# v3_Tensegrity_Motherboard.net
KiCad netlist of a schematic drawn in EAGLE
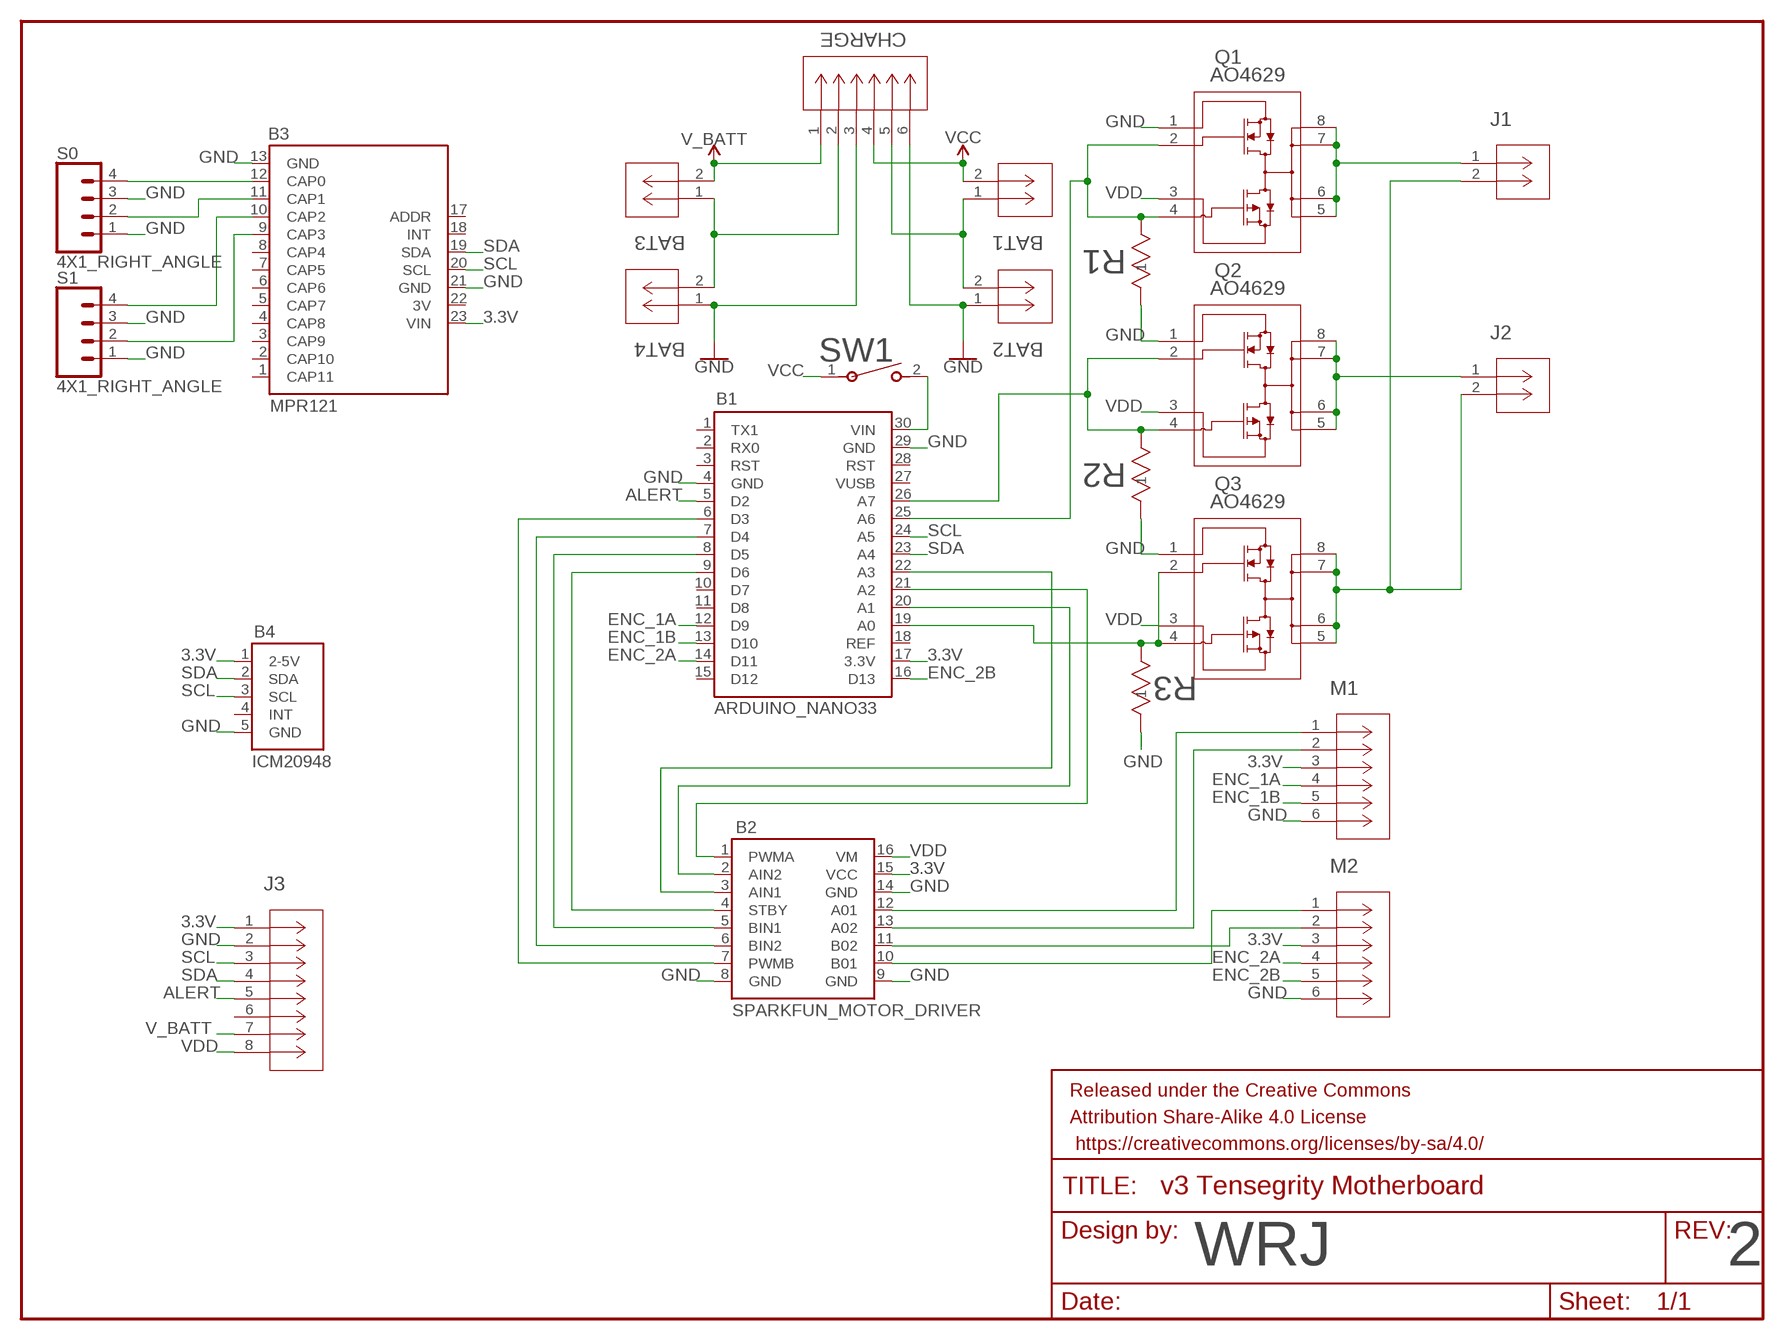
[diagram p0: schematic, sheet 1]

(export (version "E")
  (design (tool "Eeschema 10.0.6"))
  (components
    (comp (ref "B1")
      (value "ARDUINO_NANO33")
      (footprint "eagle-import:HDRVR30W64P1524X254_2X15_3810X1778X851B")
      (libsource (lib "eagle-import") (part "ARDUINO_NANO33"))
    )
    (comp (ref "B2")
      (value "SPARKFUN_MOTOR_DRIVER")
      (footprint "eagle-import:HDRVR16W64P1524X254_2X8_2032X2032X254B")
      (libsource (lib "eagle-import") (part "SPARKFUN_MOTOR_DRIVER"))
    )
    (comp (ref "B3")
      (value "MPR121")
      (footprint "eagle-import:HDRVR26W64P1524X254_2X13_3302X1905X851B")
      (libsource (lib "eagle-import") (part "MPR121"))
    )
    (comp (ref "B4")
      (value "ICM20948")
      (footprint "eagle-import:HDRVR5W64P254_1X5_1270X254X851B")
      (libsource (lib "eagle-import") (part "ICM20948"))
    )
    (comp (ref "BAT1")
      (value "S2B-PH-K-S(LF)(SN)")
      (footprint "eagle-import:CONN_S2B-PH-K-S_JST")
      (fields (field (name "COPYRIGHT") "Copyright (C) 2024 Ultra Librarian. All rights reserved."))
      (libsource (lib "eagle-import") (part "S2B-PH-K-S(LF)(SN)"))
    )
    (comp (ref "BAT2")
      (value "S2B-PH-K-S(LF)(SN)")
      (footprint "eagle-import:CONN_S2B-PH-K-S_JST")
      (fields (field (name "COPYRIGHT") "Copyright (C) 2024 Ultra Librarian. All rights reserved."))
      (libsource (lib "eagle-import") (part "S2B-PH-K-S(LF)(SN)"))
    )
    (comp (ref "BAT3")
      (value "S2B-PH-K-S(LF)(SN)")
      (footprint "eagle-import:CONN_S2B-PH-K-S_JST")
      (fields (field (name "COPYRIGHT") "Copyright (C) 2024 Ultra Librarian. All rights reserved."))
      (libsource (lib "eagle-import") (part "S2B-PH-K-S(LF)(SN)"))
    )
    (comp (ref "BAT4")
      (value "S2B-PH-K-S(LF)(SN)")
      (footprint "eagle-import:CONN_S2B-PH-K-S_JST")
      (fields (field (name "COPYRIGHT") "Copyright (C) 2024 Ultra Librarian. All rights reserved."))
      (libsource (lib "eagle-import") (part "S2B-PH-K-S(LF)(SN)"))
    )
    (comp (ref "CHARGE")
      (value "S6B-XH-A")
      (footprint "eagle-import:CONN_S6B-XH-A_JST")
      (fields (field (name "COPYRIGHT") "Copyright (C) 2024 Ultra Librarian. All rights reserved."))
      (libsource (lib "eagle-import") (part "S6B-XH-A"))
    )
    (comp (ref "FRAME1")
      (value "FRAME-LETTER")
      (footprint "eagle-import:CREATIVE_COMMONS")
      (libsource (lib "eagle-import") (part "FRAME-LETTER"))
    )
    (comp (ref "J1")
      (value "S2B-XH-A-1(LF)(SN)")
      (footprint "eagle-import:CONN_S2B-XH-A-1(LF)(SN)_JST")
      (fields (field (name "COPYRIGHT") "Copyright (C) 2024 Ultra Librarian. All rights reserved."))
      (libsource (lib "eagle-import") (part "S2B-XH-A-1(LF)(SN)"))
    )
    (comp (ref "J2")
      (value "S2B-XH-A-1(LF)(SN)")
      (footprint "eagle-import:CONN_S2B-XH-A-1(LF)(SN)_JST")
      (fields (field (name "COPYRIGHT") "Copyright (C) 2024 Ultra Librarian. All rights reserved."))
      (libsource (lib "eagle-import") (part "S2B-XH-A-1(LF)(SN)"))
    )
    (comp (ref "J3")
      (value "PEC08SAAN")
      (footprint "eagle-import:CONN_XXC08SAAN_SUL")
      (fields (field (name "COPYRIGHT") "Copyright (C) 2024 Ultra Librarian. All rights reserved."))
      (libsource (lib "eagle-import") (part "PEC08SAAN"))
    )
    (comp (ref "M1")
      (value "BM06B-SRSS-TB(LF)(SN)")
      (footprint "eagle-import:CONN_BM06B-SRSS-TB_JST")
      (fields (field (name "COPYRIGHT") "Copyright (C) 2024 Ultra Librarian. All rights reserved."))
      (libsource (lib "eagle-import") (part "BM06B-SRSS-TB(LF)(SN)"))
    )
    (comp (ref "M2")
      (value "BM06B-SRSS-TB(LF)(SN)")
      (footprint "eagle-import:CONN_BM06B-SRSS-TB_JST")
      (fields (field (name "COPYRIGHT") "Copyright (C) 2024 Ultra Librarian. All rights reserved."))
      (libsource (lib "eagle-import") (part "BM06B-SRSS-TB(LF)(SN)"))
    )
    (comp (ref "Q1")
      (value "AO4629")
      (footprint "eagle-import:SO8(SOP-8L)_AOS")
      (fields (field (name "COPYRIGHT") "Copyright (C) 2024 Ultra Librarian. All rights reserved."))
      (libsource (lib "eagle-import") (part "AO4629"))
    )
    (comp (ref "Q2")
      (value "AO4629")
      (footprint "eagle-import:SO8(SOP-8L)_AOS")
      (fields (field (name "COPYRIGHT") "Copyright (C) 2024 Ultra Librarian. All rights reserved."))
      (libsource (lib "eagle-import") (part "AO4629"))
    )
    (comp (ref "Q3")
      (value "AO4629")
      (footprint "eagle-import:SO8(SOP-8L)_AOS")
      (fields (field (name "COPYRIGHT") "Copyright (C) 2024 Ultra Librarian. All rights reserved."))
      (libsource (lib "eagle-import") (part "AO4629"))
    )
    (comp (ref "R1")
      (value "RC0603FR-071KL")
      (footprint "eagle-import:RC0603N_YAG")
      (fields (field (name "COPYRIGHT") "Copyright (C) 2024 Ultra Librarian. All rights reserved."))
      (libsource (lib "eagle-import") (part "RC0603FR-071KL"))
    )
    (comp (ref "R2")
      (value "RC0603FR-071KL")
      (footprint "eagle-import:RC0603N_YAG")
      (fields (field (name "COPYRIGHT") "Copyright (C) 2024 Ultra Librarian. All rights reserved."))
      (libsource (lib "eagle-import") (part "RC0603FR-071KL"))
    )
    (comp (ref "R3")
      (value "RC0603FR-071KL")
      (footprint "eagle-import:RC0603N_YAG")
      (fields (field (name "COPYRIGHT") "Copyright (C) 2024 Ultra Librarian. All rights reserved."))
      (libsource (lib "eagle-import") (part "RC0603FR-071KL"))
    )
    (comp (ref "S0")
      (value "4X1_RIGHT_ANGLE")
      (footprint "eagle-import:HDRRA4W64P254_1X4_1016X254X278B")
      (libsource (lib "eagle-import") (part "4X1_RIGHT_ANGLE"))
    )
    (comp (ref "S1")
      (value "4X1_RIGHT_ANGLE")
      (footprint "eagle-import:HDRRA4W64P254_1X4_1016X254X278B")
      (libsource (lib "eagle-import") (part "4X1_RIGHT_ANGLE"))
    )
    (comp (ref "SW1")
      (value "GPTS203212B")
      (footprint "eagle-import:SW_GPTS203212B_CWI")
      (fields (field (name "COPYRIGHT") "Copyright (C) 2024 Ultra Librarian. All rights reserved."))
      (libsource (lib "eagle-import") (part "GPTS203212B"))
    )
  )
  (nets
    (net (code "1") (name "/3.3V") (class "Default")
      (node (ref "B1") (pin "17") (pinfunction "3.3V_17") (pintype "power_in"))
      (node (ref "B2") (pin "15") (pinfunction "VCC_15") (pintype "power_in"))
      (node (ref "B3") (pin "23") (pinfunction "VIN_23") (pintype "power_in"))
      (node (ref "B4") (pin "1") (pinfunction "2-5V_1") (pintype "power_in"))
      (node (ref "J3") (pin "1") (pinfunction "1_1") (pintype "passive"))
      (node (ref "M1") (pin "3") (pinfunction "3_3") (pintype "passive"))
      (node (ref "M2") (pin "3") (pinfunction "3_3") (pintype "passive"))
    )
    (net (code "2") (name "/3V") (class "Default")
      (node (ref "B3") (pin "22") (pinfunction "3V_22") (pintype "power_in"))
    )
    (net (code "3") (name "/ALERT") (class "Default")
      (node (ref "B1") (pin "5") (pinfunction "D2_5") (pintype "bidirectional"))
      (node (ref "J3") (pin "5") (pinfunction "5_5") (pintype "passive"))
    )
    (net (code "4") (name "/ENC_1A") (class "Default")
      (node (ref "B1") (pin "12") (pinfunction "D9_12") (pintype "bidirectional"))
      (node (ref "M1") (pin "4") (pinfunction "4_4") (pintype "passive"))
    )
    (net (code "5") (name "/ENC_1B") (class "Default")
      (node (ref "B1") (pin "13") (pinfunction "D10_13") (pintype "bidirectional"))
      (node (ref "M1") (pin "5") (pinfunction "5_5") (pintype "passive"))
    )
    (net (code "6") (name "/ENC_2A") (class "Default")
      (node (ref "B1") (pin "14") (pinfunction "D11_14") (pintype "bidirectional"))
      (node (ref "M2") (pin "4") (pinfunction "4_4") (pintype "passive"))
    )
    (net (code "7") (name "/ENC_2B") (class "Default")
      (node (ref "B1") (pin "16") (pinfunction "D13_16") (pintype "bidirectional"))
      (node (ref "M2") (pin "5") (pinfunction "5_5") (pintype "passive"))
    )
    (net (code "8") (name "/SCL") (class "Default")
      (node (ref "B1") (pin "24") (pinfunction "A5_24") (pintype "bidirectional"))
      (node (ref "B3") (pin "20") (pinfunction "SCL_20") (pintype "bidirectional"))
      (node (ref "B4") (pin "3") (pinfunction "SCL_3") (pintype "bidirectional"))
      (node (ref "J3") (pin "3") (pinfunction "3_3") (pintype "passive"))
    )
    (net (code "9") (name "/SDA") (class "Default")
      (node (ref "B1") (pin "23") (pinfunction "A4_23") (pintype "bidirectional"))
      (node (ref "B3") (pin "19") (pinfunction "SDA_19") (pintype "bidirectional"))
      (node (ref "B4") (pin "2") (pinfunction "SDA_2") (pintype "bidirectional"))
      (node (ref "J3") (pin "4") (pinfunction "4_4") (pintype "passive"))
    )
    (net (code "10") (name "/VDD") (class "Default")
      (node (ref "B2") (pin "16") (pinfunction "VM_16") (pintype "power_in"))
      (node (ref "J3") (pin "8") (pinfunction "8_8") (pintype "passive"))
      (node (ref "Q1") (pin "3") (pinfunction "3_3") (pintype "passive"))
      (node (ref "Q2") (pin "3") (pinfunction "3_3") (pintype "passive"))
      (node (ref "Q3") (pin "3") (pinfunction "3_3") (pintype "passive"))
    )
    (net (code "11") (name "/VUSB") (class "Default")
      (node (ref "B1") (pin "27") (pinfunction "VUSB_27") (pintype "power_in"))
    )
    (net (code "12") (name "GND") (class "Default")
      (node (ref "B1") (pin "29") (pinfunction "GND_29") (pintype "power_in"))
      (node (ref "B1") (pin "4") (pinfunction "GND_4") (pintype "power_in"))
      (node (ref "B2") (pin "14") (pinfunction "GND_14") (pintype "power_in"))
      (node (ref "B2") (pin "8") (pinfunction "GND_8") (pintype "power_in"))
      (node (ref "B2") (pin "9") (pinfunction "GND_9") (pintype "power_in"))
      (node (ref "B3") (pin "13") (pinfunction "GND_13") (pintype "power_in"))
      (node (ref "B3") (pin "21") (pinfunction "GND_21") (pintype "power_in"))
      (node (ref "B4") (pin "5") (pinfunction "GND_5") (pintype "power_in"))
      (node (ref "BAT2") (pin "1") (pinfunction "1_1") (pintype "passive"))
      (node (ref "BAT4") (pin "1") (pinfunction "1_1") (pintype "passive"))
      (node (ref "CHARGE") (pin "3") (pinfunction "3_3") (pintype "passive"))
      (node (ref "CHARGE") (pin "6") (pinfunction "6_6") (pintype "passive"))
      (node (ref "J3") (pin "2") (pinfunction "2_2") (pintype "passive"))
      (node (ref "M1") (pin "6") (pinfunction "6_6") (pintype "passive"))
      (node (ref "M2") (pin "6") (pinfunction "6_6") (pintype "passive"))
      (node (ref "Q1") (pin "1") (pinfunction "1_1") (pintype "passive"))
      (node (ref "Q2") (pin "1") (pinfunction "1_1") (pintype "passive"))
      (node (ref "Q3") (pin "1") (pinfunction "1_1") (pintype "passive"))
      (node (ref "R1") (pin "1") (pinfunction "1_1") (pintype "passive"))
      (node (ref "R2") (pin "1") (pinfunction "1_1") (pintype "passive"))
      (node (ref "R3") (pin "1") (pinfunction "1_1") (pintype "passive"))
      (node (ref "S0") (pin "1") (pinfunction "1_1") (pintype "passive"))
      (node (ref "S0") (pin "3") (pinfunction "3_3") (pintype "passive"))
      (node (ref "S1") (pin "1") (pinfunction "1_1") (pintype "passive"))
      (node (ref "S1") (pin "3") (pinfunction "3_3") (pintype "passive"))
    )
    (net (code "13") (name "Net-(B1-A0)") (class "Default")
      (node (ref "B1") (pin "19") (pinfunction "A0_19") (pintype "bidirectional"))
      (node (ref "Q3") (pin "2") (pinfunction "2_2") (pintype "passive"))
      (node (ref "Q3") (pin "4") (pinfunction "4_4") (pintype "passive"))
      (node (ref "R3") (pin "2") (pinfunction "2_2") (pintype "passive"))
    )
    (net (code "14") (name "Net-(B1-A1)") (class "Default")
      (node (ref "B1") (pin "20") (pinfunction "A1_20") (pintype "bidirectional"))
      (node (ref "B2") (pin "2") (pinfunction "AIN2_2") (pintype "input"))
    )
    (net (code "15") (name "Net-(B1-A2)") (class "Default")
      (node (ref "B1") (pin "21") (pinfunction "A2_21") (pintype "bidirectional"))
      (node (ref "B2") (pin "1") (pinfunction "PWMA_1") (pintype "input"))
    )
    (net (code "16") (name "Net-(B1-A3)") (class "Default")
      (node (ref "B1") (pin "22") (pinfunction "A3_22") (pintype "bidirectional"))
      (node (ref "B2") (pin "3") (pinfunction "AIN1_3") (pintype "input"))
    )
    (net (code "17") (name "Net-(B1-A6)") (class "Default")
      (node (ref "B1") (pin "25") (pinfunction "A6_25") (pintype "bidirectional"))
      (node (ref "Q1") (pin "2") (pinfunction "2_2") (pintype "passive"))
      (node (ref "Q1") (pin "4") (pinfunction "4_4") (pintype "passive"))
      (node (ref "R1") (pin "2") (pinfunction "2_2") (pintype "passive"))
    )
    (net (code "18") (name "Net-(B1-A7)") (class "Default")
      (node (ref "B1") (pin "26") (pinfunction "A7_26") (pintype "bidirectional"))
      (node (ref "Q2") (pin "2") (pinfunction "2_2") (pintype "passive"))
      (node (ref "Q2") (pin "4") (pinfunction "4_4") (pintype "passive"))
      (node (ref "R2") (pin "2") (pinfunction "2_2") (pintype "passive"))
    )
    (net (code "19") (name "Net-(B1-D3)") (class "Default")
      (node (ref "B1") (pin "6") (pinfunction "D3_6") (pintype "bidirectional"))
      (node (ref "B2") (pin "7") (pinfunction "PWMB_7") (pintype "input"))
    )
    (net (code "20") (name "Net-(B1-D4)") (class "Default")
      (node (ref "B1") (pin "7") (pinfunction "D4_7") (pintype "bidirectional"))
      (node (ref "B2") (pin "6") (pinfunction "BIN2_6") (pintype "input"))
    )
    (net (code "21") (name "Net-(B1-D5)") (class "Default")
      (node (ref "B1") (pin "8") (pinfunction "D5_8") (pintype "bidirectional"))
      (node (ref "B2") (pin "5") (pinfunction "BIN1_5") (pintype "input"))
    )
    (net (code "22") (name "Net-(B1-D6)") (class "Default")
      (node (ref "B1") (pin "9") (pinfunction "D6_9") (pintype "bidirectional"))
      (node (ref "B2") (pin "4") (pinfunction "STBY_4") (pintype "input"))
    )
    (net (code "23") (name "Net-(B1-VIN)") (class "Default")
      (node (ref "B1") (pin "30") (pinfunction "VIN_30") (pintype "power_in"))
      (node (ref "SW1") (pin "2") (pinfunction "2_2") (pintype "passive"))
    )
    (net (code "24") (name "Net-(B2-A01)") (class "Default")
      (node (ref "B2") (pin "12") (pinfunction "A01_12") (pintype "output"))
      (node (ref "M1") (pin "1") (pinfunction "1_1") (pintype "passive"))
    )
    (net (code "25") (name "Net-(B2-A02)") (class "Default")
      (node (ref "B2") (pin "13") (pinfunction "A02_13") (pintype "output"))
      (node (ref "M1") (pin "2") (pinfunction "2_2") (pintype "passive"))
    )
    (net (code "26") (name "Net-(B2-B01)") (class "Default")
      (node (ref "B2") (pin "10") (pinfunction "B01_10") (pintype "output"))
      (node (ref "M2") (pin "1") (pinfunction "1_1") (pintype "passive"))
    )
    (net (code "27") (name "Net-(B2-B02)") (class "Default")
      (node (ref "B2") (pin "11") (pinfunction "B02_11") (pintype "output"))
      (node (ref "M2") (pin "2") (pinfunction "2_2") (pintype "passive"))
    )
    (net (code "28") (name "Net-(B3-CAP0)") (class "Default")
      (node (ref "B3") (pin "12") (pinfunction "CAP0_12") (pintype "input"))
      (node (ref "S0") (pin "4") (pinfunction "4_4") (pintype "passive"))
    )
    (net (code "29") (name "Net-(B3-CAP1)") (class "Default")
      (node (ref "B3") (pin "11") (pinfunction "CAP1_11") (pintype "input"))
      (node (ref "S0") (pin "2") (pinfunction "2_2") (pintype "passive"))
    )
    (net (code "30") (name "Net-(B3-CAP2)") (class "Default")
      (node (ref "B3") (pin "10") (pinfunction "CAP2_10") (pintype "input"))
      (node (ref "S1") (pin "4") (pinfunction "4_4") (pintype "passive"))
    )
    (net (code "31") (name "Net-(B3-CAP3)") (class "Default")
      (node (ref "B3") (pin "9") (pinfunction "CAP3_9") (pintype "input"))
      (node (ref "S1") (pin "2") (pinfunction "2_2") (pintype "passive"))
    )
    (net (code "32") (name "Net-(BAT1-Pad1)") (class "Default")
      (node (ref "BAT1") (pin "1") (pinfunction "1_1") (pintype "passive"))
      (node (ref "BAT2") (pin "2") (pinfunction "2_2") (pintype "passive"))
      (node (ref "CHARGE") (pin "5") (pinfunction "5_5") (pintype "passive"))
    )
    (net (code "33") (name "Net-(BAT3-Pad1)") (class "Default")
      (node (ref "BAT3") (pin "1") (pinfunction "1_1") (pintype "passive"))
      (node (ref "BAT4") (pin "2") (pinfunction "2_2") (pintype "passive"))
      (node (ref "CHARGE") (pin "2") (pinfunction "2_2") (pintype "passive"))
    )
    (net (code "34") (name "Net-(J1-Pad1)") (class "Default")
      (node (ref "J1") (pin "1") (pinfunction "1_1") (pintype "passive"))
      (node (ref "Q1") (pin "5") (pinfunction "5_5") (pintype "passive"))
      (node (ref "Q1") (pin "6") (pinfunction "6_6") (pintype "passive"))
      (node (ref "Q1") (pin "7") (pinfunction "7_7") (pintype "passive"))
      (node (ref "Q1") (pin "8") (pinfunction "8_8") (pintype "passive"))
    )
    (net (code "35") (name "Net-(J1-Pad2)") (class "Default")
      (node (ref "J1") (pin "2") (pinfunction "2_2") (pintype "passive"))
      (node (ref "J2") (pin "2") (pinfunction "2_2") (pintype "passive"))
      (node (ref "Q3") (pin "5") (pinfunction "5_5") (pintype "passive"))
      (node (ref "Q3") (pin "6") (pinfunction "6_6") (pintype "passive"))
      (node (ref "Q3") (pin "7") (pinfunction "7_7") (pintype "passive"))
      (node (ref "Q3") (pin "8") (pinfunction "8_8") (pintype "passive"))
    )
    (net (code "36") (name "Net-(J2-Pad1)") (class "Default")
      (node (ref "J2") (pin "1") (pinfunction "1_1") (pintype "passive"))
      (node (ref "Q2") (pin "5") (pinfunction "5_5") (pintype "passive"))
      (node (ref "Q2") (pin "6") (pinfunction "6_6") (pintype "passive"))
      (node (ref "Q2") (pin "7") (pinfunction "7_7") (pintype "passive"))
      (node (ref "Q2") (pin "8") (pinfunction "8_8") (pintype "passive"))
    )
    (net (code "37") (name "VCC") (class "Default")
      (node (ref "BAT1") (pin "2") (pinfunction "2_2") (pintype "passive"))
      (node (ref "CHARGE") (pin "4") (pinfunction "4_4") (pintype "passive"))
      (node (ref "SW1") (pin "1") (pinfunction "1_1") (pintype "passive"))
    )
    (net (code "38") (name "V_BATT") (class "Default")
      (node (ref "BAT3") (pin "2") (pinfunction "2_2") (pintype "passive"))
      (node (ref "CHARGE") (pin "1") (pinfunction "1_1") (pintype "passive"))
      (node (ref "J3") (pin "7") (pinfunction "7_7") (pintype "passive"))
    )
    (net (code "39") (name "unconnected-(B1-D7-Pad10)") (class "Default")
      (node (ref "B1") (pin "10") (pinfunction "D7_10") (pintype "bidirectional"))
    )
    (net (code "40") (name "unconnected-(B1-D8-Pad11)") (class "Default")
      (node (ref "B1") (pin "11") (pinfunction "D8_11") (pintype "bidirectional"))
    )
    (net (code "41") (name "unconnected-(B1-D12-Pad15)") (class "Default")
      (node (ref "B1") (pin "15") (pinfunction "D12_15") (pintype "bidirectional"))
    )
    (net (code "42") (name "unconnected-(B1-REF-Pad18)") (class "Default")
      (node (ref "B1") (pin "18") (pinfunction "REF_18") (pintype "bidirectional"))
    )
    (net (code "43") (name "unconnected-(B1-RST-Pad3)") (class "Default")
      (node (ref "B1") (pin "3") (pinfunction "RST_3") (pintype "bidirectional"))
    )
    (net (code "44") (name "unconnected-(B1-RST-Pad28)") (class "Default")
      (node (ref "B1") (pin "28") (pinfunction "RST_28") (pintype "bidirectional"))
    )
    (net (code "45") (name "unconnected-(B1-RX0-Pad2)") (class "Default")
      (node (ref "B1") (pin "2") (pinfunction "RX0_2") (pintype "bidirectional"))
    )
    (net (code "46") (name "unconnected-(B1-TX1-Pad1)") (class "Default")
      (node (ref "B1") (pin "1") (pinfunction "TX1_1") (pintype "bidirectional"))
    )
    (net (code "47") (name "unconnected-(B3-ADDR-Pad17)") (class "Default")
      (node (ref "B3") (pin "17") (pinfunction "ADDR_17") (pintype "bidirectional"))
    )
    (net (code "48") (name "unconnected-(B3-CAP4-Pad8)") (class "Default")
      (node (ref "B3") (pin "8") (pinfunction "CAP4_8") (pintype "input"))
    )
    (net (code "49") (name "unconnected-(B3-CAP5-Pad7)") (class "Default")
      (node (ref "B3") (pin "7") (pinfunction "CAP5_7") (pintype "input"))
    )
    (net (code "50") (name "unconnected-(B3-CAP6-Pad6)") (class "Default")
      (node (ref "B3") (pin "6") (pinfunction "CAP6_6") (pintype "input"))
    )
    (net (code "51") (name "unconnected-(B3-CAP7-Pad5)") (class "Default")
      (node (ref "B3") (pin "5") (pinfunction "CAP7_5") (pintype "input"))
    )
    (net (code "52") (name "unconnected-(B3-CAP8-Pad4)") (class "Default")
      (node (ref "B3") (pin "4") (pinfunction "CAP8_4") (pintype "input"))
    )
    (net (code "53") (name "unconnected-(B3-CAP9-Pad3)") (class "Default")
      (node (ref "B3") (pin "3") (pinfunction "CAP9_3") (pintype "input"))
    )
    (net (code "54") (name "unconnected-(B3-CAP10-Pad2)") (class "Default")
      (node (ref "B3") (pin "2") (pinfunction "CAP10_2") (pintype "input"))
    )
    (net (code "55") (name "unconnected-(B3-CAP11-Pad1)") (class "Default")
      (node (ref "B3") (pin "1") (pinfunction "CAP11_1") (pintype "input"))
    )
    (net (code "56") (name "unconnected-(B3-INT-Pad18)") (class "Default")
      (node (ref "B3") (pin "18") (pinfunction "INT_18") (pintype "bidirectional"))
    )
    (net (code "57") (name "unconnected-(B4-INT-Pad4)") (class "Default")
      (node (ref "B4") (pin "4") (pinfunction "INT_4") (pintype "bidirectional"))
    )
    (net (code "58") (name "unconnected-(J3-Pad6)") (class "Default")
      (node (ref "J3") (pin "6") (pinfunction "6_6") (pintype "passive"))
    )
  )
)
